# SAMDi_version4.net
KiCad netlist of a schematic drawn in EAGLE
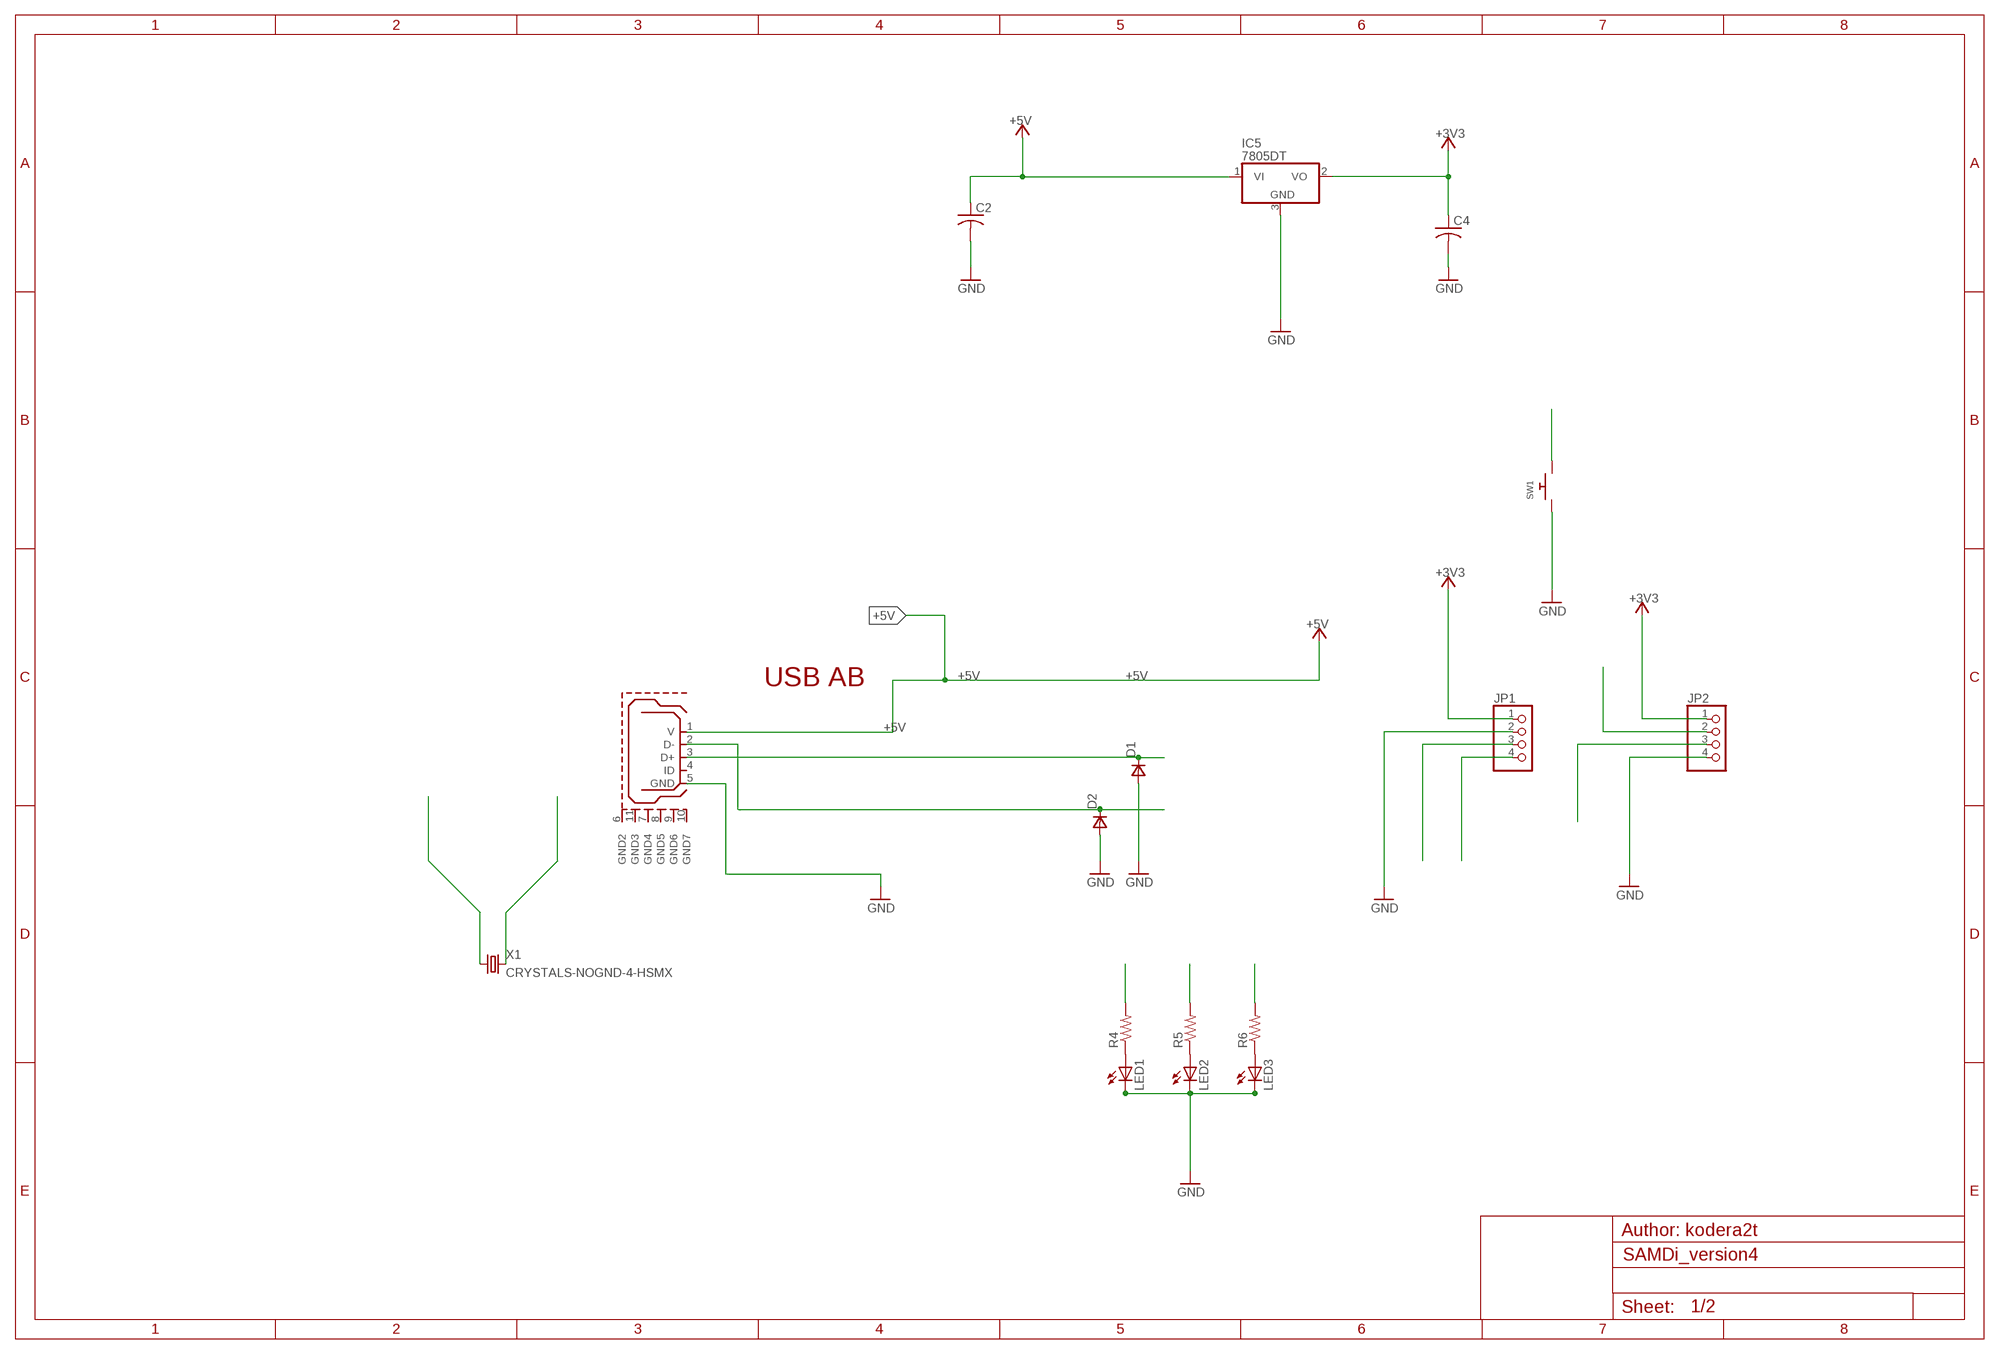
[diagram p0: schematic, sheet 1]
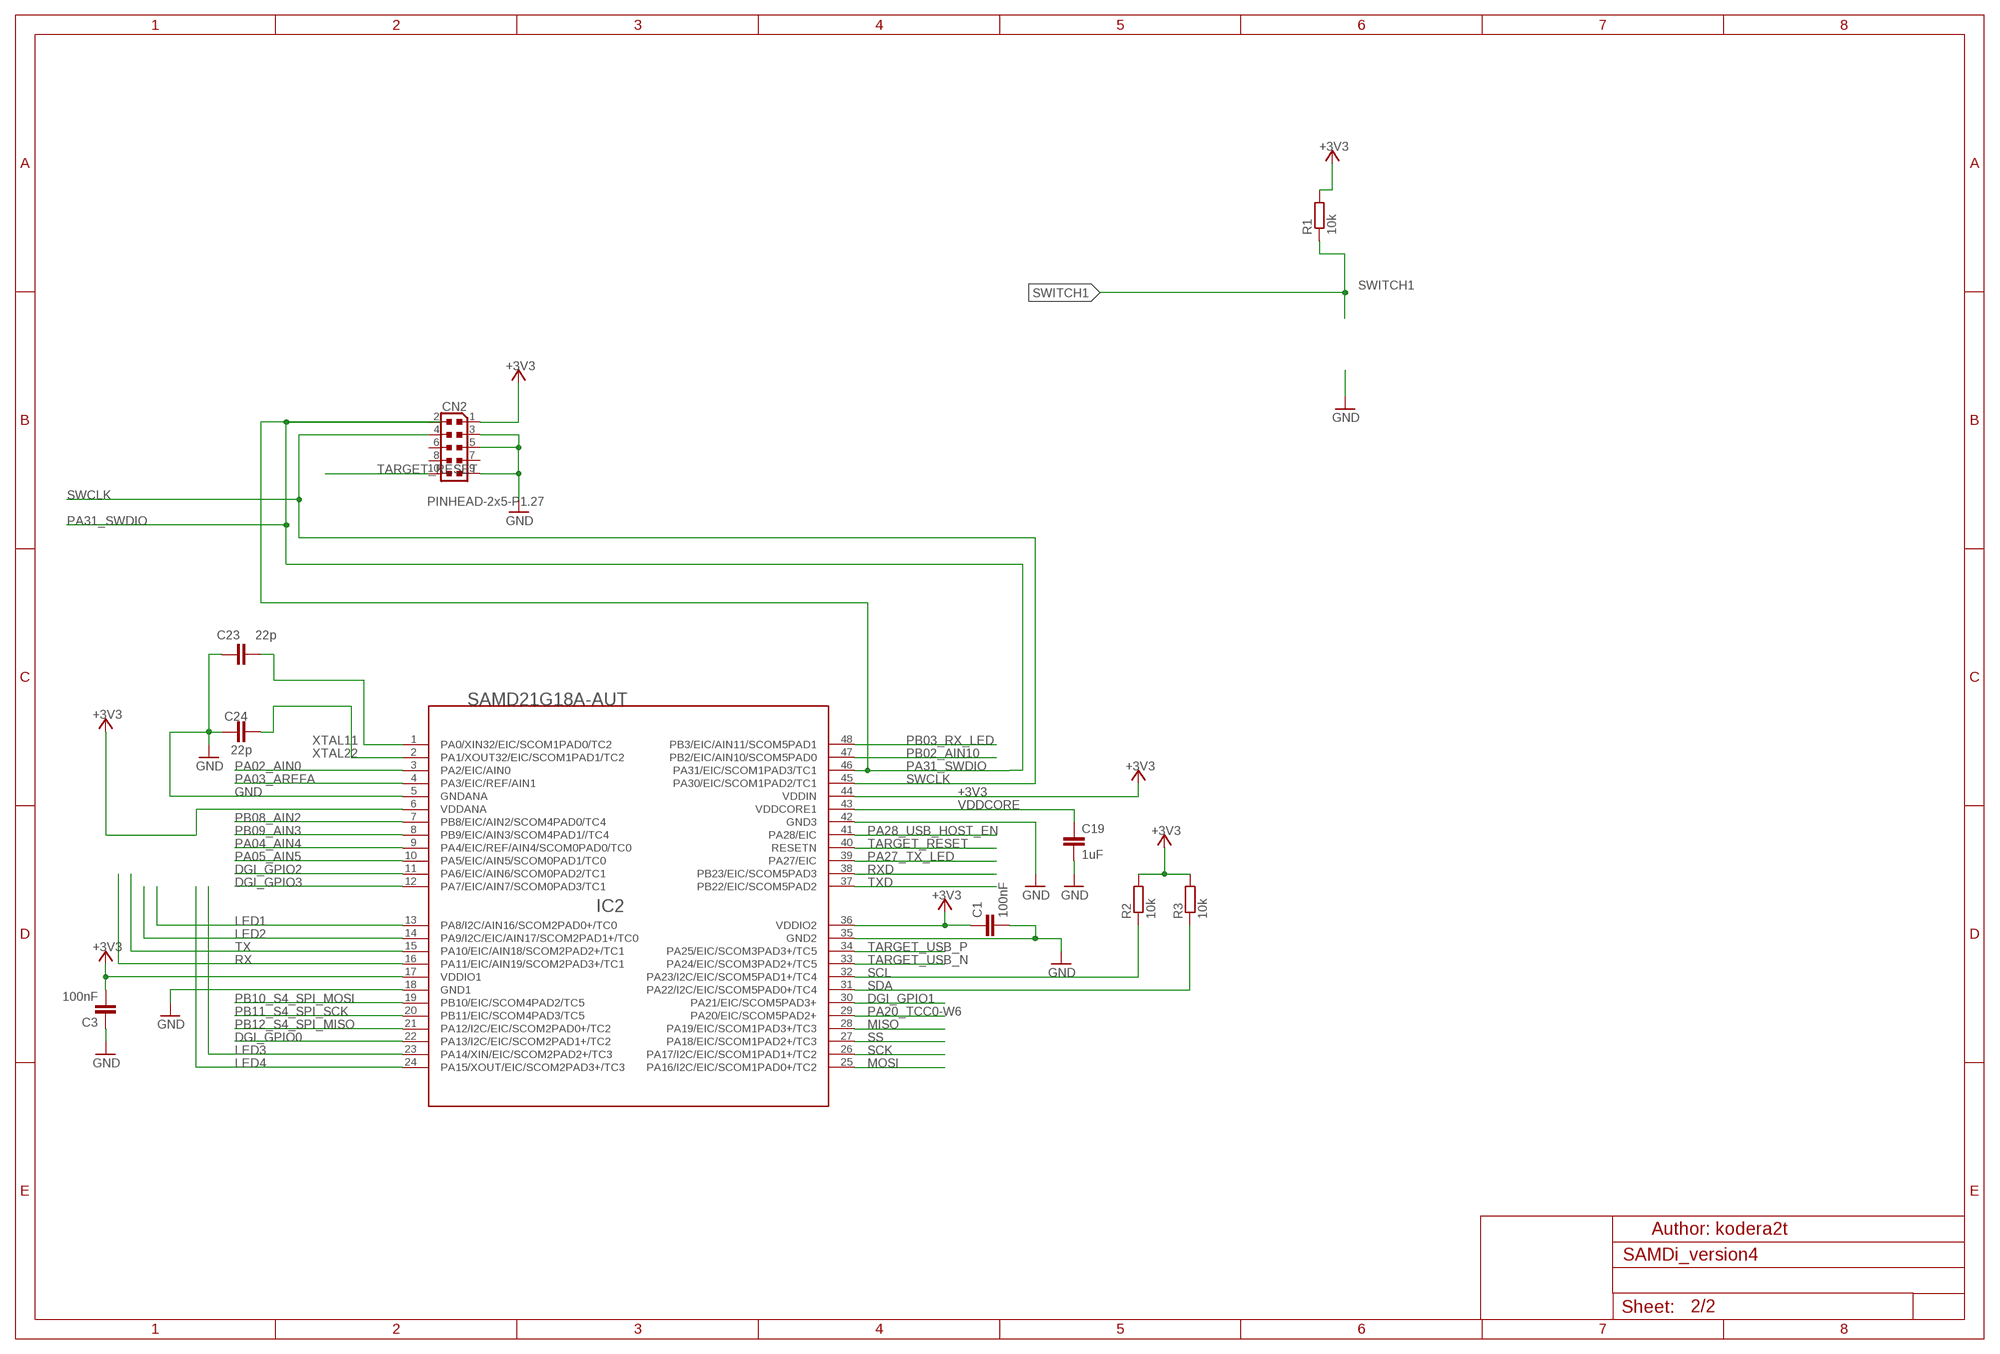
[diagram p1: schematic, sheet 2]

(export (version "E")
  (design (tool "Eeschema 10.0.6"))
  (components
    (comp (ref "C1")
      (value "100nF")
      (footprint "eagle-import:C0603-ROUND")
      (fields (field (name "PART_NUMBER") "cl10b104kbnc"))
      (libsource (lib "eagle-import") (part "0015_100NF_0603"))
    )
    (comp (ref "C3")
      (value "100nF")
      (footprint "eagle-import:C0603-ROUND")
      (fields (field (name "PART_NUMBER") "cl10b104kbnc"))
      (libsource (lib "eagle-import") (part "0015_100NF_0603"))
    )
    (comp (ref "C19")
      (value "1uF")
      (footprint "eagle-import:C0603-ROUND")
      (fields (field (name "PART_NUMBER") "1uF_0603/GRM188R61E105KA12D"))
      (libsource (lib "eagle-import") (part "0006_1UF_0603/GRM188R61E105KA12D"))
    )
    (comp (ref "C23")
      (value "22p")
      (footprint "eagle-import:C0603-ROUND")
      (fields (field (name "PART_NUMBER") "22pF_0603"))
      (libsource (lib "eagle-import") (part "0014_22PF_0603"))
    )
    (comp (ref "C24")
      (value "22p")
      (footprint "eagle-import:C0603-ROUND")
      (fields (field (name "PART_NUMBER") "22pF_0603"))
      (libsource (lib "eagle-import") (part "0014_22PF_0603"))
    )
    (comp (ref "CN2")
      (value "PINHEAD-2x5-P1.27")
      (footprint "eagle-import:PINHEAD_2X05_127")
      (libsource (lib "eagle-import") (part "0171_PH127-205DF055G00AROUND-PADS"))
    )
    (comp (ref "IC2")
      (value "SAMD21G18A-AUT")
      (footprint "eagle-import:TQFP48-7X7")
      (libsource (lib "eagle-import") (part "1792_SAMD21G18A-AUT"))
    )
    (comp (ref "R1")
      (value "10k")
      (footprint "eagle-import:R0603-ROUND")
      (fields (field (name "PART_NUMBER") "CR0603JW103L"))
      (libsource (lib "eagle-import") (part "0028_CR0603JW103L"))
    )
    (comp (ref "R2")
      (value "10k")
      (footprint "eagle-import:R0603-ROUND")
      (fields (field (name "PART_NUMBER") "CR0603JW103L"))
      (libsource (lib "eagle-import") (part "0028_CR0603JW103L"))
    )
    (comp (ref "R3")
      (value "10k")
      (footprint "eagle-import:R0603-ROUND")
      (fields (field (name "PART_NUMBER") "CR0603JW103L"))
      (libsource (lib "eagle-import") (part "0028_CR0603JW103L"))
    )
    (comp (ref "C2")
      (value "C-USC0603")
      (footprint "eagle-import:C0603")
      (libsource (lib "eagle-import") (part "C-USC0603"))
    )
    (comp (ref "C4")
      (value "C-USC0603")
      (footprint "eagle-import:C0603")
      (libsource (lib "eagle-import") (part "C-USC0603"))
    )
    (comp (ref "D1")
      (value "DSOD323")
      (footprint "eagle-import:SOD323")
      (fields (field (name "MPN") "CDSOD323-T05C"))
      (libsource (lib "eagle-import") (part "DSOD323"))
    )
    (comp (ref "D2")
      (value "DSOD323")
      (footprint "eagle-import:SOD323")
      (fields (field (name "MPN") "CDSOD323-T05C"))
      (libsource (lib "eagle-import") (part "DSOD323"))
    )
    (comp (ref "IC5")
      (value "7805DT")
      (footprint "eagle-import:TO252")
      (libsource (lib "eagle-import") (part "78DT05"))
    )
    (comp (ref "JP1")
      (value "HEADER-1X4")
      (footprint "eagle-import:1X04_OVAL")
      (libsource (lib "eagle-import") (part "HEADER-1X4"))
    )
    (comp (ref "JP2")
      (value "PINHD-1X4")
      (footprint "eagle-import:1X04")
      (libsource (lib "eagle-import") (part "PINHD-1X4"))
    )
    (comp (ref "LED1")
      (value "LEDCHIP-LED0603")
      (footprint "eagle-import:CHIP-LED0603")
      (libsource (lib "eagle-import") (part "LEDCHIP-LED0603"))
    )
    (comp (ref "LED2")
      (value "LEDCHIP-LED0603")
      (footprint "eagle-import:CHIP-LED0603")
      (libsource (lib "eagle-import") (part "LEDCHIP-LED0603"))
    )
    (comp (ref "LED3")
      (value "LEDCHIP-LED0603")
      (footprint "eagle-import:CHIP-LED0603")
      (libsource (lib "eagle-import") (part "LEDCHIP-LED0603"))
    )
    (comp (ref "R4")
      (value "R-US_R0603")
      (footprint "eagle-import:R0603")
      (libsource (lib "eagle-import") (part "R-US_R0603"))
    )
    (comp (ref "R5")
      (value "R-US_R0603")
      (footprint "eagle-import:R0603")
      (libsource (lib "eagle-import") (part "R-US_R0603"))
    )
    (comp (ref "R6")
      (value "R-US_R0603")
      (footprint "eagle-import:R0603")
      (libsource (lib "eagle-import") (part "R-US_R0603"))
    )
    (comp (ref "SW1")
      (value "SWITCH_PUSHBUTTONSOFTTOUCHSMD_SJ")
      (footprint "eagle-import:PUSHBUTTON_SMD_SJ")
      (libsource (lib "eagle-import") (part "SWITCH_PUSHBUTTONSOFTTOUCHSMD_SJ"))
    )
    (comp (ref "U$1")
      (value "USB_MICROB")
      (footprint "eagle-import:USB_MICROB_PACKAGE")
      (libsource (lib "eagle-import") (part "USB_MICROB"))
    )
    (comp (ref "X1")
      (value "CRYSTALS-NOGND-4-HSMX")
      (footprint "eagle-import:HC49-4-HSMX")
      (libsource (lib "eagle-import") (part "CRYSTALS-NOGND-4-HSMX"))
    )
  )
  (nets
    (net (code "1") (name "+3V3") (class "Default")
      (node (ref "C1") (pin "1") (pinfunction "1_1") (pintype "passive"))
      (node (ref "C3") (pin "2") (pinfunction "2_2") (pintype "passive"))
      (node (ref "C4") (pin "1") (pinfunction "1_1") (pintype "passive"))
      (node (ref "CN2") (pin "1") (pinfunction "1_1") (pintype "passive"))
      (node (ref "IC2") (pin "17") (pinfunction "VDDIO1_17") (pintype "power_in"))
      (node (ref "IC2") (pin "36") (pinfunction "VDDIO2_36") (pintype "power_in"))
      (node (ref "IC2") (pin "44") (pinfunction "VDDIN_44") (pintype "power_in"))
      (node (ref "IC2") (pin "6") (pinfunction "VDDANA_6") (pintype "power_in"))
      (node (ref "IC5") (pin "2") (pinfunction "VO_2") (pintype "passive"))
      (node (ref "JP1") (pin "1") (pinfunction "1_1") (pintype "passive"))
      (node (ref "JP2") (pin "1") (pinfunction "1_1") (pintype "passive"))
      (node (ref "R1") (pin "2") (pinfunction "2_2") (pintype "passive"))
      (node (ref "R2") (pin "2") (pinfunction "2_2") (pintype "passive"))
      (node (ref "R3") (pin "2") (pinfunction "2_2") (pintype "passive"))
    )
    (net (code "2") (name "+5V") (class "Default")
      (node (ref "C2") (pin "1") (pinfunction "1_1") (pintype "passive"))
      (node (ref "IC5") (pin "1") (pinfunction "VI_1") (pintype "input"))
      (node (ref "U$1") (pin "1") (pinfunction "V_1") (pintype "bidirectional"))
    )
    (net (code "3") (name "DGI_GPIO0") (class "Default")
      (node (ref "IC2") (pin "22") (pinfunction "PA13/I2C/EIC/SCOM2PAD1+/TC2_22") (pintype "bidirectional"))
    )
    (net (code "4") (name "DGI_GPIO1") (class "Default")
      (node (ref "IC2") (pin "30") (pinfunction "PA21/EIC/SCOM5PAD3+_30") (pintype "bidirectional"))
    )
    (net (code "5") (name "DGI_GPIO2") (class "Default")
      (node (ref "IC2") (pin "11") (pinfunction "PA6/EIC/AIN6/SCOM0PAD2/TC1_11") (pintype "bidirectional"))
    )
    (net (code "6") (name "DGI_GPIO3") (class "Default")
      (node (ref "IC2") (pin "12") (pinfunction "PA7/EIC/AIN7/SCOM0PAD3/TC1_12") (pintype "bidirectional"))
    )
    (net (code "7") (name "GND") (class "Default")
      (node (ref "C1") (pin "2") (pinfunction "2_2") (pintype "passive"))
      (node (ref "C19") (pin "2") (pinfunction "2_2") (pintype "passive"))
      (node (ref "C2") (pin "2") (pinfunction "2_2") (pintype "passive"))
      (node (ref "C23") (pin "1") (pinfunction "1_1") (pintype "passive"))
      (node (ref "C24") (pin "1") (pinfunction "1_1") (pintype "passive"))
      (node (ref "C3") (pin "1") (pinfunction "1_1") (pintype "passive"))
      (node (ref "C4") (pin "2") (pinfunction "2_2") (pintype "passive"))
      (node (ref "CN2") (pin "3") (pinfunction "3_3") (pintype "passive"))
      (node (ref "CN2") (pin "5") (pinfunction "5_5") (pintype "passive"))
      (node (ref "CN2") (pin "9") (pinfunction "9_9") (pintype "passive"))
      (node (ref "D1") (pin "2") (pinfunction "A_2") (pintype "passive"))
      (node (ref "D2") (pin "2") (pinfunction "A_2") (pintype "passive"))
      (node (ref "IC2") (pin "18") (pinfunction "GND1_18") (pintype "power_in"))
      (node (ref "IC2") (pin "35") (pinfunction "GND2_35") (pintype "power_in"))
      (node (ref "IC2") (pin "42") (pinfunction "GND3_42") (pintype "power_in"))
      (node (ref "IC2") (pin "5") (pinfunction "GNDANA_5") (pintype "power_in"))
      (node (ref "IC5") (pin "3") (pinfunction "GND_3") (pintype "passive"))
      (node (ref "JP1") (pin "2") (pinfunction "2_2") (pintype "passive"))
      (node (ref "JP2") (pin "4") (pinfunction "4_4") (pintype "passive"))
      (node (ref "LED1") (pin "C") (pinfunction "C_C") (pintype "passive"))
      (node (ref "LED2") (pin "C") (pinfunction "C_C") (pintype "passive"))
      (node (ref "LED3") (pin "C") (pinfunction "C_C") (pintype "passive"))
      (node (ref "SW1") (pin "P$1") (pinfunction "P$1_P$1") (pintype "passive"))
      (node (ref "U$1") (pin "5") (pinfunction "GND_5") (pintype "bidirectional"))
    )
    (net (code "8") (name "LED1") (class "Default")
      (node (ref "IC2") (pin "13") (pinfunction "PA8/I2C/AIN16/SCOM2PAD0+/TC0_13") (pintype "bidirectional"))
      (node (ref "R4") (pin "2") (pinfunction "2_2") (pintype "passive"))
    )
    (net (code "9") (name "LED2") (class "Default")
      (node (ref "IC2") (pin "14") (pinfunction "PA9/I2C/EIC/AIN17/SCOM2PAD1+/TC0_14") (pintype "bidirectional"))
      (node (ref "R5") (pin "2") (pinfunction "2_2") (pintype "passive"))
    )
    (net (code "10") (name "LED3") (class "Default")
      (node (ref "IC2") (pin "23") (pinfunction "PA14/XIN/EIC/SCOM2PAD2+/TC3_23") (pintype "bidirectional"))
      (node (ref "R6") (pin "2") (pinfunction "2_2") (pintype "passive"))
    )
    (net (code "11") (name "LED4") (class "Default")
      (node (ref "IC2") (pin "24") (pinfunction "PA15/XOUT/EIC/SCOM2PAD3+/TC3_24") (pintype "bidirectional"))
    )
    (net (code "12") (name "MISO") (class "Default")
      (node (ref "IC2") (pin "28") (pinfunction "PA19/EIC/SCOM1PAD3+/TC3_28") (pintype "bidirectional"))
    )
    (net (code "13") (name "MOSI") (class "Default")
      (node (ref "IC2") (pin "25") (pinfunction "PA16/I2C/EIC/SCOM1PAD0+/TC2_25") (pintype "bidirectional"))
    )
    (net (code "14") (name "Net-(LED1-PadA)") (class "Default")
      (node (ref "LED1") (pin "A") (pinfunction "A_A") (pintype "passive"))
      (node (ref "R4") (pin "1") (pinfunction "1_1") (pintype "passive"))
    )
    (net (code "15") (name "Net-(LED2-PadA)") (class "Default")
      (node (ref "LED2") (pin "A") (pinfunction "A_A") (pintype "passive"))
      (node (ref "R5") (pin "1") (pinfunction "1_1") (pintype "passive"))
    )
    (net (code "16") (name "Net-(LED3-PadA)") (class "Default")
      (node (ref "LED3") (pin "A") (pinfunction "A_A") (pintype "passive"))
      (node (ref "R6") (pin "1") (pinfunction "1_1") (pintype "passive"))
    )
    (net (code "17") (name "PA02_AIN0") (class "Default")
      (node (ref "IC2") (pin "3") (pinfunction "PA2/EIC/AIN0_3") (pintype "bidirectional"))
    )
    (net (code "18") (name "PA03_AREFA") (class "Default")
      (node (ref "IC2") (pin "4") (pinfunction "PA3/EIC/REF/AIN1_4") (pintype "bidirectional"))
    )
    (net (code "19") (name "PA04_AIN4") (class "Default")
      (node (ref "IC2") (pin "9") (pinfunction "PA4/EIC/REF/AIN4/SCOM0PAD0/TC0_9") (pintype "bidirectional"))
    )
    (net (code "20") (name "PA05_AIN5") (class "Default")
      (node (ref "IC2") (pin "10") (pinfunction "PA5/EIC/AIN5/SCOM0PAD1/TC0_10") (pintype "bidirectional"))
    )
    (net (code "21") (name "PA20_TCC0-W6") (class "Default")
      (node (ref "IC2") (pin "29") (pinfunction "PA20/EIC/SCOM5PAD2+_29") (pintype "bidirectional"))
    )
    (net (code "22") (name "PA27_TX_LED") (class "Default")
      (node (ref "IC2") (pin "39") (pinfunction "PA27/EIC_39") (pintype "bidirectional"))
    )
    (net (code "23") (name "PA28_USB_HOST_EN") (class "Default")
      (node (ref "IC2") (pin "41") (pinfunction "PA28/EIC_41") (pintype "bidirectional"))
    )
    (net (code "24") (name "PA31_SWDIO") (class "Default")
      (node (ref "CN2") (pin "2") (pinfunction "2_2") (pintype "passive"))
      (node (ref "IC2") (pin "46") (pinfunction "PA31/EIC/SCOM1PAD3/TC1_46") (pintype "bidirectional"))
    )
    (net (code "25") (name "PB02_AIN10") (class "Default")
      (node (ref "IC2") (pin "47") (pinfunction "PB2/EIC/AIN10/SCOM5PAD0_47") (pintype "bidirectional"))
    )
    (net (code "26") (name "PB03_RX_LED") (class "Default")
      (node (ref "IC2") (pin "48") (pinfunction "PB3/EIC/AIN11/SCOM5PAD1_48") (pintype "bidirectional"))
    )
    (net (code "27") (name "PB08_AIN2") (class "Default")
      (node (ref "IC2") (pin "7") (pinfunction "PB8/EIC/AIN2/SCOM4PAD0/TC4_7") (pintype "bidirectional"))
    )
    (net (code "28") (name "PB09_AIN3") (class "Default")
      (node (ref "IC2") (pin "8") (pinfunction "PB9/EIC/AIN3/SCOM4PAD1//TC4_8") (pintype "bidirectional"))
    )
    (net (code "29") (name "PB10_S4_SPI_MOSI") (class "Default")
      (node (ref "IC2") (pin "19") (pinfunction "PB10/EIC/SCOM4PAD2/TC5_19") (pintype "bidirectional"))
    )
    (net (code "30") (name "PB11_S4_SPI_SCK") (class "Default")
      (node (ref "IC2") (pin "20") (pinfunction "PB11/EIC/SCOM4PAD3/TC5_20") (pintype "bidirectional"))
    )
    (net (code "31") (name "PB12_S4_SPI_MISO") (class "Default")
      (node (ref "IC2") (pin "21") (pinfunction "PA12/I2C/EIC/SCOM2PAD0+/TC2_21") (pintype "bidirectional"))
    )
    (net (code "32") (name "RX") (class "Default")
      (node (ref "IC2") (pin "16") (pinfunction "PA11/EIC/AIN19/SCOM2PAD3+/TC1_16") (pintype "bidirectional"))
      (node (ref "JP2") (pin "3") (pinfunction "3_3") (pintype "passive"))
    )
    (net (code "33") (name "RXD") (class "Default")
      (node (ref "IC2") (pin "38") (pinfunction "PB23/EIC/SCOM5PAD3_38") (pintype "bidirectional"))
    )
    (net (code "34") (name "SCK") (class "Default")
      (node (ref "IC2") (pin "26") (pinfunction "PA17/I2C/EIC/SCOM1PAD1+/TC2_26") (pintype "bidirectional"))
    )
    (net (code "35") (name "SCL") (class "Default")
      (node (ref "IC2") (pin "32") (pinfunction "PA23/I2C/EIC/SCOM5PAD1+/TC4_32") (pintype "bidirectional"))
      (node (ref "JP1") (pin "3") (pinfunction "3_3") (pintype "passive"))
      (node (ref "R2") (pin "1") (pinfunction "1_1") (pintype "passive"))
    )
    (net (code "36") (name "SDA") (class "Default")
      (node (ref "IC2") (pin "31") (pinfunction "PA22/I2C/EIC/SCOM5PAD0+/TC4_31") (pintype "bidirectional"))
      (node (ref "JP1") (pin "4") (pinfunction "4_4") (pintype "passive"))
      (node (ref "R3") (pin "1") (pinfunction "1_1") (pintype "passive"))
    )
    (net (code "37") (name "SS") (class "Default")
      (node (ref "IC2") (pin "27") (pinfunction "PA18/EIC/SCOM1PAD2+/TC3_27") (pintype "bidirectional"))
    )
    (net (code "38") (name "SWCLK") (class "Default")
      (node (ref "CN2") (pin "4") (pinfunction "4_4") (pintype "passive"))
      (node (ref "IC2") (pin "45") (pinfunction "PA30/EIC/SCOM1PAD2/TC1_45") (pintype "bidirectional"))
    )
    (net (code "39") (name "SWITCH1") (class "Default")
      (node (ref "R1") (pin "1") (pinfunction "1_1") (pintype "passive"))
      (node (ref "SW1") (pin "P$2") (pinfunction "P$2_P$2") (pintype "passive"))
    )
    (net (code "40") (name "TARGET_RESET") (class "Default")
      (node (ref "CN2") (pin "10") (pinfunction "10_10") (pintype "passive"))
      (node (ref "IC2") (pin "40") (pinfunction "RESETN_40") (pintype "bidirectional"))
    )
    (net (code "41") (name "TARGET_USB_N") (class "Default")
      (node (ref "D2") (pin "1") (pinfunction "C_1") (pintype "passive"))
      (node (ref "IC2") (pin "33") (pinfunction "PA24/EIC/SCOM3PAD2+/TC5_33") (pintype "bidirectional"))
      (node (ref "U$1") (pin "2") (pinfunction "D-_2") (pintype "bidirectional"))
    )
    (net (code "42") (name "TARGET_USB_P") (class "Default")
      (node (ref "D1") (pin "1") (pinfunction "C_1") (pintype "passive"))
      (node (ref "IC2") (pin "34") (pinfunction "PA25/EIC/SCOM3PAD3+/TC5_34") (pintype "bidirectional"))
      (node (ref "U$1") (pin "3") (pinfunction "D+_3") (pintype "bidirectional"))
    )
    (net (code "43") (name "TX") (class "Default")
      (node (ref "IC2") (pin "15") (pinfunction "PA10/EIC/AIN18/SCOM2PAD2+/TC1_15") (pintype "bidirectional"))
      (node (ref "JP2") (pin "2") (pinfunction "2_2") (pintype "passive"))
    )
    (net (code "44") (name "TXD") (class "Default")
      (node (ref "IC2") (pin "37") (pinfunction "PB22/EIC/SCOM5PAD2_37") (pintype "bidirectional"))
    )
    (net (code "45") (name "VDDCORE") (class "Default")
      (node (ref "C19") (pin "1") (pinfunction "1_1") (pintype "passive"))
      (node (ref "IC2") (pin "43") (pinfunction "VDDCORE1_43") (pintype "input"))
    )
    (net (code "46") (name "XTAL11") (class "Default")
      (node (ref "C23") (pin "2") (pinfunction "2_2") (pintype "passive"))
      (node (ref "IC2") (pin "1") (pinfunction "PA0/XIN32/EIC/SCOM1PAD0/TC2_1") (pintype "bidirectional"))
      (node (ref "X1") (pin "2") (pinfunction "2_2") (pintype "passive"))
    )
    (net (code "47") (name "XTAL22") (class "Default")
      (node (ref "C24") (pin "2") (pinfunction "2_2") (pintype "passive"))
      (node (ref "IC2") (pin "2") (pinfunction "PA1/XOUT32/EIC/SCOM1PAD1/TC2_2") (pintype "bidirectional"))
      (node (ref "X1") (pin "1") (pinfunction "1_1") (pintype "passive"))
    )
    (net (code "48") (name "unconnected-(CN2-Pad6)") (class "Default")
      (node (ref "CN2") (pin "6") (pinfunction "6_6") (pintype "passive"))
    )
    (net (code "49") (name "unconnected-(CN2-Pad7)") (class "Default")
      (node (ref "CN2") (pin "7") (pinfunction "7_7") (pintype "passive"))
    )
    (net (code "50") (name "unconnected-(CN2-Pad8)") (class "Default")
      (node (ref "CN2") (pin "8") (pinfunction "8_8") (pintype "passive"))
    )
    (net (code "51") (name "unconnected-(U$1-GND2-Pad6)") (class "Default")
      (node (ref "U$1") (pin "6") (pinfunction "GND2_6") (pintype "bidirectional"))
    )
    (net (code "52") (name "unconnected-(U$1-GND3-Pad11)") (class "Default")
      (node (ref "U$1") (pin "11") (pinfunction "GND3_11") (pintype "bidirectional"))
    )
    (net (code "53") (name "unconnected-(U$1-GND4-Pad7)") (class "Default")
      (node (ref "U$1") (pin "7") (pinfunction "GND4_7") (pintype "bidirectional"))
    )
    (net (code "54") (name "unconnected-(U$1-GND5-Pad8)") (class "Default")
      (node (ref "U$1") (pin "8") (pinfunction "GND5_8") (pintype "bidirectional"))
    )
    (net (code "55") (name "unconnected-(U$1-GND6-Pad9)") (class "Default")
      (node (ref "U$1") (pin "9") (pinfunction "GND6_9") (pintype "bidirectional"))
    )
    (net (code "56") (name "unconnected-(U$1-GND7-Pad10)") (class "Default")
      (node (ref "U$1") (pin "10") (pinfunction "GND7_10") (pintype "bidirectional"))
    )
    (net (code "57") (name "unconnected-(U$1-ID-Pad4)") (class "Default")
      (node (ref "U$1") (pin "4") (pinfunction "ID_4") (pintype "bidirectional"))
    )
  )
)
